# XADC_Example.net
KiCad netlist of a schematic drawn in EAGLE
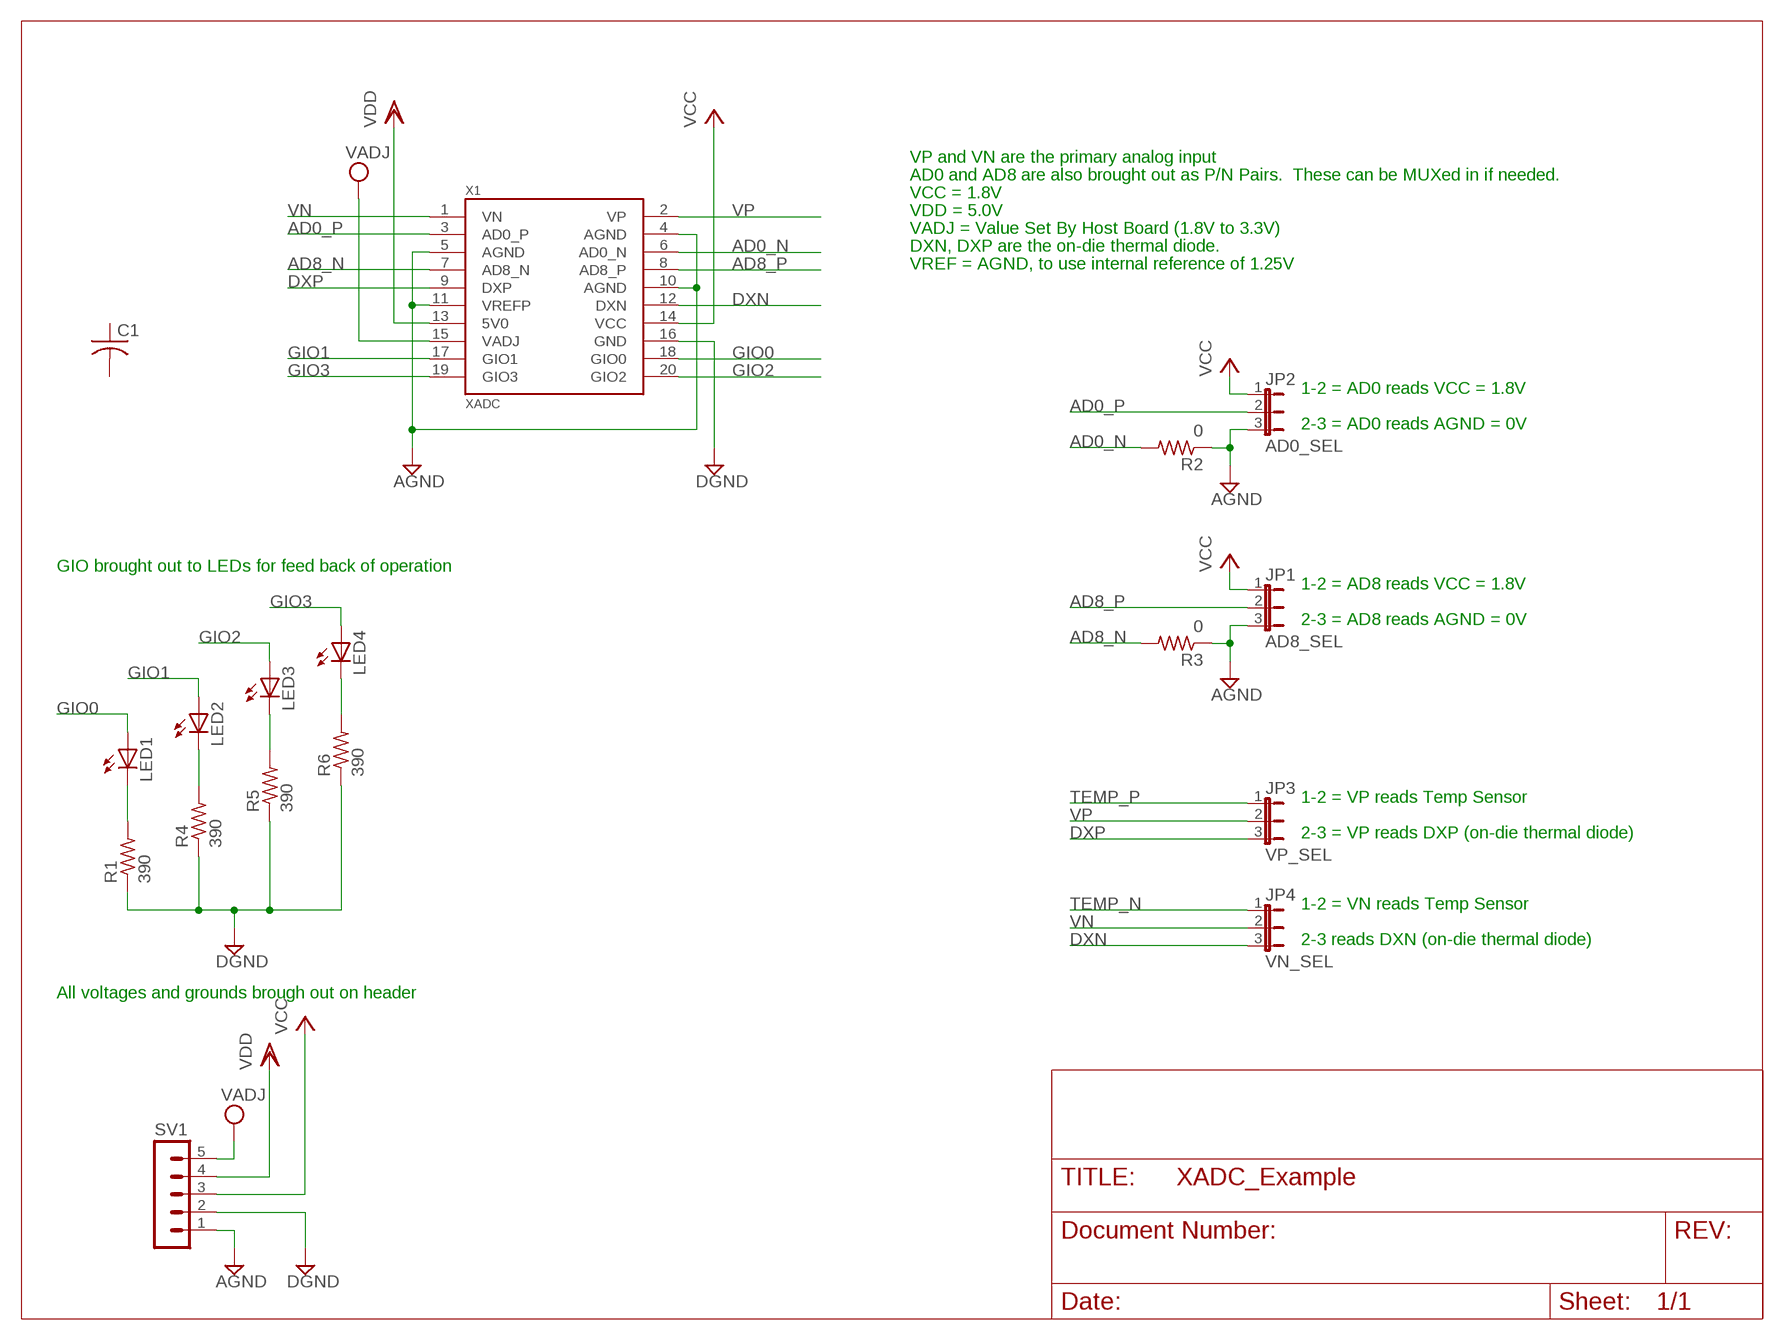
[diagram p0: schematic, sheet 1]

(export (version "E")
  (design (tool "Eeschema 10.0.6"))
  (components
    (comp (ref "C1")
      (value "C-USC0603")
      (footprint "eagle-import:C0603")
      (libsource (lib "eagle-import") (part "C-USC0603"))
    )
    (comp (ref "JP1")
      (value "AD8_SEL")
      (footprint "eagle-import:JP2")
      (libsource (lib "eagle-import") (part "JP2E"))
    )
    (comp (ref "JP2")
      (value "AD0_SEL")
      (footprint "eagle-import:JP2")
      (libsource (lib "eagle-import") (part "JP2E"))
    )
    (comp (ref "JP3")
      (value "VP_SEL")
      (footprint "eagle-import:JP2")
      (libsource (lib "eagle-import") (part "JP2E"))
    )
    (comp (ref "JP4")
      (value "VN_SEL")
      (footprint "eagle-import:JP2")
      (libsource (lib "eagle-import") (part "JP2E"))
    )
    (comp (ref "LED1")
      (value "LED5MM")
      (footprint "eagle-import:LED5MM")
      (libsource (lib "eagle-import") (part "LED5MM"))
    )
    (comp (ref "LED2")
      (value "LED5MM")
      (footprint "eagle-import:LED5MM")
      (libsource (lib "eagle-import") (part "LED5MM"))
    )
    (comp (ref "LED3")
      (value "LED5MM")
      (footprint "eagle-import:LED5MM")
      (libsource (lib "eagle-import") (part "LED5MM"))
    )
    (comp (ref "LED4")
      (value "LED5MM")
      (footprint "eagle-import:LED5MM")
      (libsource (lib "eagle-import") (part "LED5MM"))
    )
    (comp (ref "R1")
      (value "390")
      (footprint "eagle-import:R0603")
      (libsource (lib "eagle-import") (part "R-US_R0603"))
    )
    (comp (ref "R2")
      (value "0")
      (footprint "eagle-import:R0603")
      (libsource (lib "eagle-import") (part "R-US_R0603"))
    )
    (comp (ref "R3")
      (value "0")
      (footprint "eagle-import:R0603")
      (libsource (lib "eagle-import") (part "R-US_R0603"))
    )
    (comp (ref "R4")
      (value "390")
      (footprint "eagle-import:R0603")
      (libsource (lib "eagle-import") (part "R-US_R0603"))
    )
    (comp (ref "R5")
      (value "390")
      (footprint "eagle-import:R0603")
      (libsource (lib "eagle-import") (part "R-US_R0603"))
    )
    (comp (ref "R6")
      (value "390")
      (footprint "eagle-import:R0603")
      (libsource (lib "eagle-import") (part "R-US_R0603"))
    )
    (comp (ref "SV1")
      (value "MA05-1")
      (footprint "eagle-import:MA05-1")
      (libsource (lib "eagle-import") (part "MA05-1"))
    )
    (comp (ref "X1")
      (value "XADC")
      (footprint "eagle-import:XADC_2X10")
      (libsource (lib "eagle-import") (part "XADC"))
    )
  )
  (nets
    (net (code "1") (name "/AD0_N") (class "Default")
      (node (ref "R2") (pin "2") (pinfunction "2_2") (pintype "passive"))
      (node (ref "X1") (pin "6") (pinfunction "AD0_N_6") (pintype "bidirectional"))
    )
    (net (code "2") (name "/AD0_P") (class "Default")
      (node (ref "JP2") (pin "2") (pinfunction "2_2") (pintype "passive"))
      (node (ref "X1") (pin "3") (pinfunction "AD0_P_3") (pintype "bidirectional"))
    )
    (net (code "3") (name "/AD8_N") (class "Default")
      (node (ref "R3") (pin "2") (pinfunction "2_2") (pintype "passive"))
      (node (ref "X1") (pin "7") (pinfunction "AD8_N_7") (pintype "bidirectional"))
    )
    (net (code "4") (name "/AD8_P") (class "Default")
      (node (ref "JP1") (pin "2") (pinfunction "2_2") (pintype "passive"))
      (node (ref "X1") (pin "8") (pinfunction "AD8_P_8") (pintype "bidirectional"))
    )
    (net (code "5") (name "/DXN") (class "Default")
      (node (ref "JP4") (pin "3") (pinfunction "3_3") (pintype "passive"))
      (node (ref "X1") (pin "12") (pinfunction "DXN_12") (pintype "bidirectional"))
    )
    (net (code "6") (name "/DXP") (class "Default")
      (node (ref "JP3") (pin "3") (pinfunction "3_3") (pintype "passive"))
      (node (ref "X1") (pin "9") (pinfunction "DXP_9") (pintype "bidirectional"))
    )
    (net (code "7") (name "/GIO0") (class "Default")
      (node (ref "LED1") (pin "A") (pinfunction "A_A") (pintype "passive"))
      (node (ref "X1") (pin "18") (pinfunction "GIO0_18") (pintype "bidirectional"))
    )
    (net (code "8") (name "/GIO1") (class "Default")
      (node (ref "LED2") (pin "A") (pinfunction "A_A") (pintype "passive"))
      (node (ref "X1") (pin "17") (pinfunction "GIO1_17") (pintype "bidirectional"))
    )
    (net (code "9") (name "/GIO2") (class "Default")
      (node (ref "LED3") (pin "A") (pinfunction "A_A") (pintype "passive"))
      (node (ref "X1") (pin "20") (pinfunction "GIO2_20") (pintype "bidirectional"))
    )
    (net (code "10") (name "/GIO3") (class "Default")
      (node (ref "LED4") (pin "A") (pinfunction "A_A") (pintype "passive"))
      (node (ref "X1") (pin "19") (pinfunction "GIO3_19") (pintype "bidirectional"))
    )
    (net (code "11") (name "/TEMP_N") (class "Default")
      (node (ref "JP4") (pin "1") (pinfunction "1_1") (pintype "passive"))
    )
    (net (code "12") (name "/TEMP_P") (class "Default")
      (node (ref "JP3") (pin "1") (pinfunction "1_1") (pintype "passive"))
    )
    (net (code "13") (name "/VN") (class "Default")
      (node (ref "JP4") (pin "2") (pinfunction "2_2") (pintype "passive"))
      (node (ref "X1") (pin "1") (pinfunction "VN_1") (pintype "bidirectional"))
    )
    (net (code "14") (name "/VP") (class "Default")
      (node (ref "JP3") (pin "2") (pinfunction "2_2") (pintype "passive"))
      (node (ref "X1") (pin "2") (pinfunction "VP_2") (pintype "bidirectional"))
    )
    (net (code "15") (name "AGND") (class "Default")
      (node (ref "JP1") (pin "3") (pinfunction "3_3") (pintype "passive"))
      (node (ref "JP2") (pin "3") (pinfunction "3_3") (pintype "passive"))
      (node (ref "R2") (pin "1") (pinfunction "1_1") (pintype "passive"))
      (node (ref "R3") (pin "1") (pinfunction "1_1") (pintype "passive"))
      (node (ref "SV1") (pin "1") (pinfunction "1_1") (pintype "passive"))
      (node (ref "X1") (pin "10") (pinfunction "AGND_10") (pintype "bidirectional"))
      (node (ref "X1") (pin "11") (pinfunction "VREFP_11") (pintype "bidirectional"))
      (node (ref "X1") (pin "4") (pinfunction "AGND_4") (pintype "bidirectional"))
      (node (ref "X1") (pin "5") (pinfunction "AGND_5") (pintype "bidirectional"))
    )
    (net (code "16") (name "DGND") (class "Default")
      (node (ref "R1") (pin "1") (pinfunction "1_1") (pintype "passive"))
      (node (ref "R4") (pin "1") (pinfunction "1_1") (pintype "passive"))
      (node (ref "R5") (pin "1") (pinfunction "1_1") (pintype "passive"))
      (node (ref "R6") (pin "1") (pinfunction "1_1") (pintype "passive"))
      (node (ref "SV1") (pin "2") (pinfunction "2_2") (pintype "passive"))
      (node (ref "X1") (pin "16") (pinfunction "GND_16") (pintype "bidirectional"))
    )
    (net (code "17") (name "Net-(LED1-C)") (class "Default")
      (node (ref "LED1") (pin "K") (pinfunction "C_K") (pintype "passive"))
      (node (ref "R1") (pin "2") (pinfunction "2_2") (pintype "passive"))
    )
    (net (code "18") (name "Net-(LED2-C)") (class "Default")
      (node (ref "LED2") (pin "K") (pinfunction "C_K") (pintype "passive"))
      (node (ref "R4") (pin "2") (pinfunction "2_2") (pintype "passive"))
    )
    (net (code "19") (name "Net-(LED3-C)") (class "Default")
      (node (ref "LED3") (pin "K") (pinfunction "C_K") (pintype "passive"))
      (node (ref "R5") (pin "2") (pinfunction "2_2") (pintype "passive"))
    )
    (net (code "20") (name "Net-(LED4-C)") (class "Default")
      (node (ref "LED4") (pin "K") (pinfunction "C_K") (pintype "passive"))
      (node (ref "R6") (pin "2") (pinfunction "2_2") (pintype "passive"))
    )
    (net (code "21") (name "VADJ") (class "Default")
      (node (ref "SV1") (pin "4") (pinfunction "4_4") (pintype "passive"))
      (node (ref "SV1") (pin "5") (pinfunction "5_5") (pintype "passive"))
      (node (ref "X1") (pin "13") (pinfunction "5V0_13") (pintype "bidirectional"))
      (node (ref "X1") (pin "15") (pinfunction "VADJ_15") (pintype "bidirectional"))
    )
    (net (code "22") (name "VCC") (class "Default")
      (node (ref "JP1") (pin "1") (pinfunction "1_1") (pintype "passive"))
      (node (ref "JP2") (pin "1") (pinfunction "1_1") (pintype "passive"))
      (node (ref "SV1") (pin "3") (pinfunction "3_3") (pintype "passive"))
      (node (ref "X1") (pin "14") (pinfunction "VCC_14") (pintype "bidirectional"))
    )
    (net (code "23") (name "unconnected-(C1-Pad1)") (class "Default")
      (node (ref "C1") (pin "1") (pinfunction "1_1") (pintype "passive"))
    )
    (net (code "24") (name "unconnected-(C1-Pad2)") (class "Default")
      (node (ref "C1") (pin "2") (pinfunction "2_2") (pintype "passive"))
    )
  )
)
